# BUCK_CONVERTER.net
KiCad netlist of a schematic drawn in Altium Designer
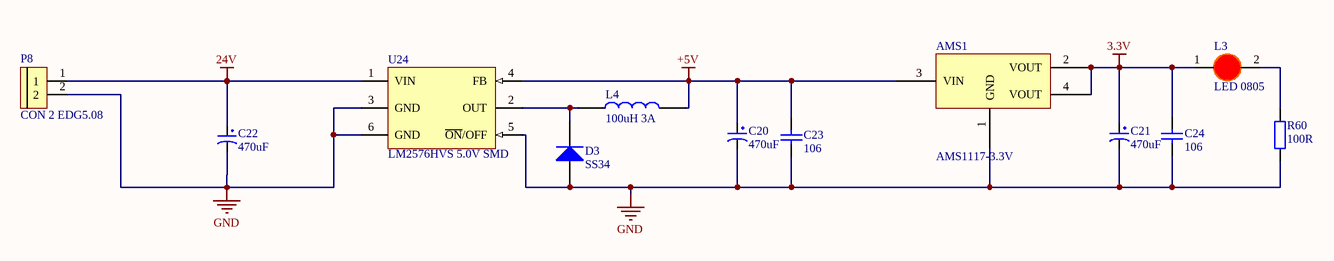
[diagram p0: BUCK CONVERTER.SchDoc]

(export (version "E")
  (design (tool "Eeschema 10.0.6"))
  (components
    (comp (ref "AMS1")
      (value "AMS1117-3.3V")
      (footprint "SOT223")
      (description "Dán")
      (libsource (lib "Altium_Lib_by_KhueNguyenCreator") (part "AMS1117 SMD"))
    )
    (comp (ref "C20")
      (value "470uF")
      (footprint "tu hoa 8mm")
      (description "Cắm")
      (libsource (lib "Altium_Lib_by_KhueNguyenCreator") (part "Tu Hoa 470uF 16V 8x11"))
    )
    (comp (ref "C21")
      (value "470uF")
      (footprint "tu hoa 8mm")
      (description "Cắm")
      (libsource (lib "Altium_Lib_by_KhueNguyenCreator") (part "Tu Hoa 470uF 16V 8x11"))
    )
    (comp (ref "C22")
      (value "470uF")
      (footprint "tu hoa 10mm")
      (description "Cắm")
      (libsource (lib "Altium_Lib_by_KhueNguyenCreator") (part "Tu Hoa 470uF 50V 10x17"))
    )
    (comp (ref "C23")
      (value "106")
      (footprint "tu 0805")
      (description "Dán")
      (libsource (lib "Altium_Lib_by_KhueNguyenCreator") (part "Tu 0805 106 16V 10%"))
    )
    (comp (ref "C24")
      (value "106")
      (footprint "tu 0805")
      (description "Dán")
      (libsource (lib "Altium_Lib_by_KhueNguyenCreator") (part "Tu 0805 106 16V 10%"))
    )
    (comp (ref "D3")
      (value "SS34")
      (footprint "DIODE SMA")
      (description "Dán")
      (libsource (lib "Altium_Lib_by_KhueNguyenCreator") (part "Diode SS34 ( 1N5822 )"))
    )
    (comp (ref "L3")
      (value "LED 0805")
      (footprint "LED-0805-Red")
      (description "Dán")
      (libsource (lib "Altium_Lib_by_KhueNguyenCreator") (part "LED 0805 Do"))
    )
    (comp (ref "L4")
      (value "100uH 3A")
      (footprint "CUON CAM 100uH3A")
      (description "Dán")
      (libsource (lib "Altium_Lib_by_KhueNguyenCreator") (part "CUON CAM 100uH DIP"))
    )
    (comp (ref "P8")
      (value "CON 2 EDG5.08")
      (footprint "CON 2 2EDG5.08")
      (description "Cắm")
      (libsource (lib "Altium_Lib_by_KhueNguyenCreator") (part "CON 2 EDG5.08"))
    )
    (comp (ref "R60")
      (value "100R")
      (footprint "tro smd 0805")
      (description "Dán")
      (libsource (lib "Altium_Lib_by_KhueNguyenCreator") (part "Tro 0805 5% 100R"))
    )
    (comp (ref "U24")
      (value "LM2576HVS 5.0V SMD")
      (footprint "TO263-5")
      (description "Dán")
      (libsource (lib "Altium_Lib_by_KhueNguyenCreator") (part "LM2576HVS 5.0V SMD"))
    )
  )
  (nets
    (net (code "1") (name "+5V") (class "Default")
      (node (ref "AMS1") (pin "3") (pinfunction "VIN_3") (pintype "passive"))
      (node (ref "C20") (pin "1") (pinfunction "1_1") (pintype "passive"))
      (node (ref "C23") (pin "2") (pinfunction "2_2") (pintype "passive"))
      (node (ref "L4") (pin "2") (pinfunction "2_2") (pintype "passive"))
      (node (ref "U24") (pin "4") (pinfunction "FB_4") (pintype "input"))
    )
    (net (code "2") (name "3.3V") (class "Default")
      (node (ref "AMS1") (pin "2") (pinfunction "VOUT_2") (pintype "passive"))
      (node (ref "AMS1") (pin "4") (pinfunction "VOUT_4") (pintype "passive"))
      (node (ref "C21") (pin "1") (pinfunction "1_1") (pintype "passive"))
      (node (ref "C24") (pin "2") (pinfunction "2_2") (pintype "passive"))
      (node (ref "L3") (pin "1") (pinfunction "A_1") (pintype "passive"))
    )
    (net (code "3") (name "24V") (class "Default")
      (node (ref "C22") (pin "1") (pinfunction "1_1") (pintype "passive"))
      (node (ref "P8") (pin "1") (pinfunction "1_1") (pintype "passive"))
      (node (ref "U24") (pin "1") (pinfunction "VIN_1") (pintype "power_in"))
    )
    (net (code "4") (name "GND") (class "Default")
      (node (ref "AMS1") (pin "1") (pinfunction "GND_1") (pintype "passive"))
      (node (ref "C20") (pin "2") (pinfunction "2_2") (pintype "passive"))
      (node (ref "C21") (pin "2") (pinfunction "2_2") (pintype "passive"))
      (node (ref "C22") (pin "2") (pinfunction "2_2") (pintype "passive"))
      (node (ref "C23") (pin "1") (pinfunction "1_1") (pintype "passive"))
      (node (ref "C24") (pin "1") (pinfunction "1_1") (pintype "passive"))
      (node (ref "D3") (pin "1") (pinfunction "A_1") (pintype "passive"))
      (node (ref "P8") (pin "2") (pinfunction "2_2") (pintype "passive"))
      (node (ref "R60") (pin "2") (pinfunction "2_2") (pintype "passive"))
      (node (ref "U24") (pin "3") (pinfunction "GND_3") (pintype "power_in"))
      (node (ref "U24") (pin "5") (pinfunction "~{ON}/OFF_5") (pintype "input"))
      (node (ref "U24") (pin "6") (pinfunction "GND_6") (pintype "passive"))
    )
    (net (code "5") (name "Net-(D3-K)") (class "Default")
      (node (ref "D3") (pin "2") (pinfunction "K_2") (pintype "passive"))
      (node (ref "L4") (pin "1") (pinfunction "1_1") (pintype "passive"))
      (node (ref "U24") (pin "2") (pinfunction "OUT_2") (pintype "power_in"))
    )
    (net (code "6") (name "Net-(L3-K)") (class "Default")
      (node (ref "L3") (pin "2") (pinfunction "K_2") (pintype "passive"))
      (node (ref "R60") (pin "1") (pinfunction "1_1") (pintype "passive"))
    )
  )
)
